# ANTENNE.net
KiCad netlist of a schematic drawn in Altium Designer
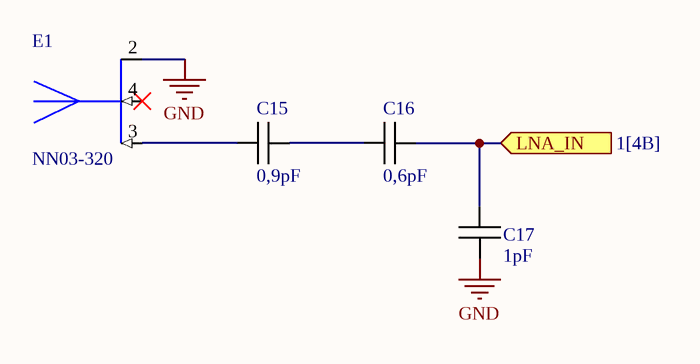
[diagram p0: ANTENNE.SchDoc]

(export (version "E")
  (design (tool "Eeschema 10.0.6"))
  (components
    (comp (ref "C15")
      (value "0,9pF")
      (footprint "CAPC1005X06N")
      (libsource (lib "SCHLibrary") (part "Capacitor"))
    )
    (comp (ref "C16")
      (value "0,6pF")
      (footprint "CAPC1005X06N")
      (libsource (lib "SCHLibrary") (part "Capacitor"))
    )
    (comp (ref "C17")
      (value "1pF")
      (footprint "CAPC1005X06N")
      (libsource (lib "SCHLibrary") (part "Capacitor"))
    )
    (comp (ref "E1")
      (value "NN03-320")
      (footprint "XCVR_NN03-320")
      (fields (field (name "MOUSER PART NUMBER") "128-NN03-320"))
      (libsource (lib "SCHLibrary") (part "NN03-320"))
    )
  )
  (nets
    (net (code "1") (name "/LNA_IN") (class "Default")
      (node (ref "C16") (pin "2") (pinfunction "2_2") (pintype "passive"))
      (node (ref "C17") (pin "2") (pinfunction "2_2") (pintype "passive"))
    )
    (net (code "2") (name "GND") (class "Default")
      (node (ref "C17") (pin "1") (pinfunction "1_1") (pintype "passive"))
      (node (ref "E1") (pin "2") (pinfunction "GROUND_2") (pintype "power_in"))
    )
    (net (code "3") (name "Net-(C15-Pad2)") (class "Default")
      (node (ref "C15") (pin "2") (pinfunction "2_2") (pintype "passive"))
      (node (ref "C16") (pin "1") (pinfunction "1_1") (pintype "passive"))
    )
    (net (code "4") (name "Net-(E1-FEED_BLUETOOTH)") (class "Default")
      (node (ref "C15") (pin "1") (pinfunction "1_1") (pintype "passive"))
      (node (ref "E1") (pin "3") (pinfunction "FEED_BLUETOOTH_3") (pintype "input"))
    )
    (net (code "5") (name "unconnected-(E1-FEED_GNSS-Pad4)") (class "Default")
      (node (ref "E1") (pin "4") (pinfunction "FEED_GNSS_4") (pintype "input+no_connect"))
    )
  )
)
